# Main.net
KiCad netlist of a schematic drawn in Altium Designer
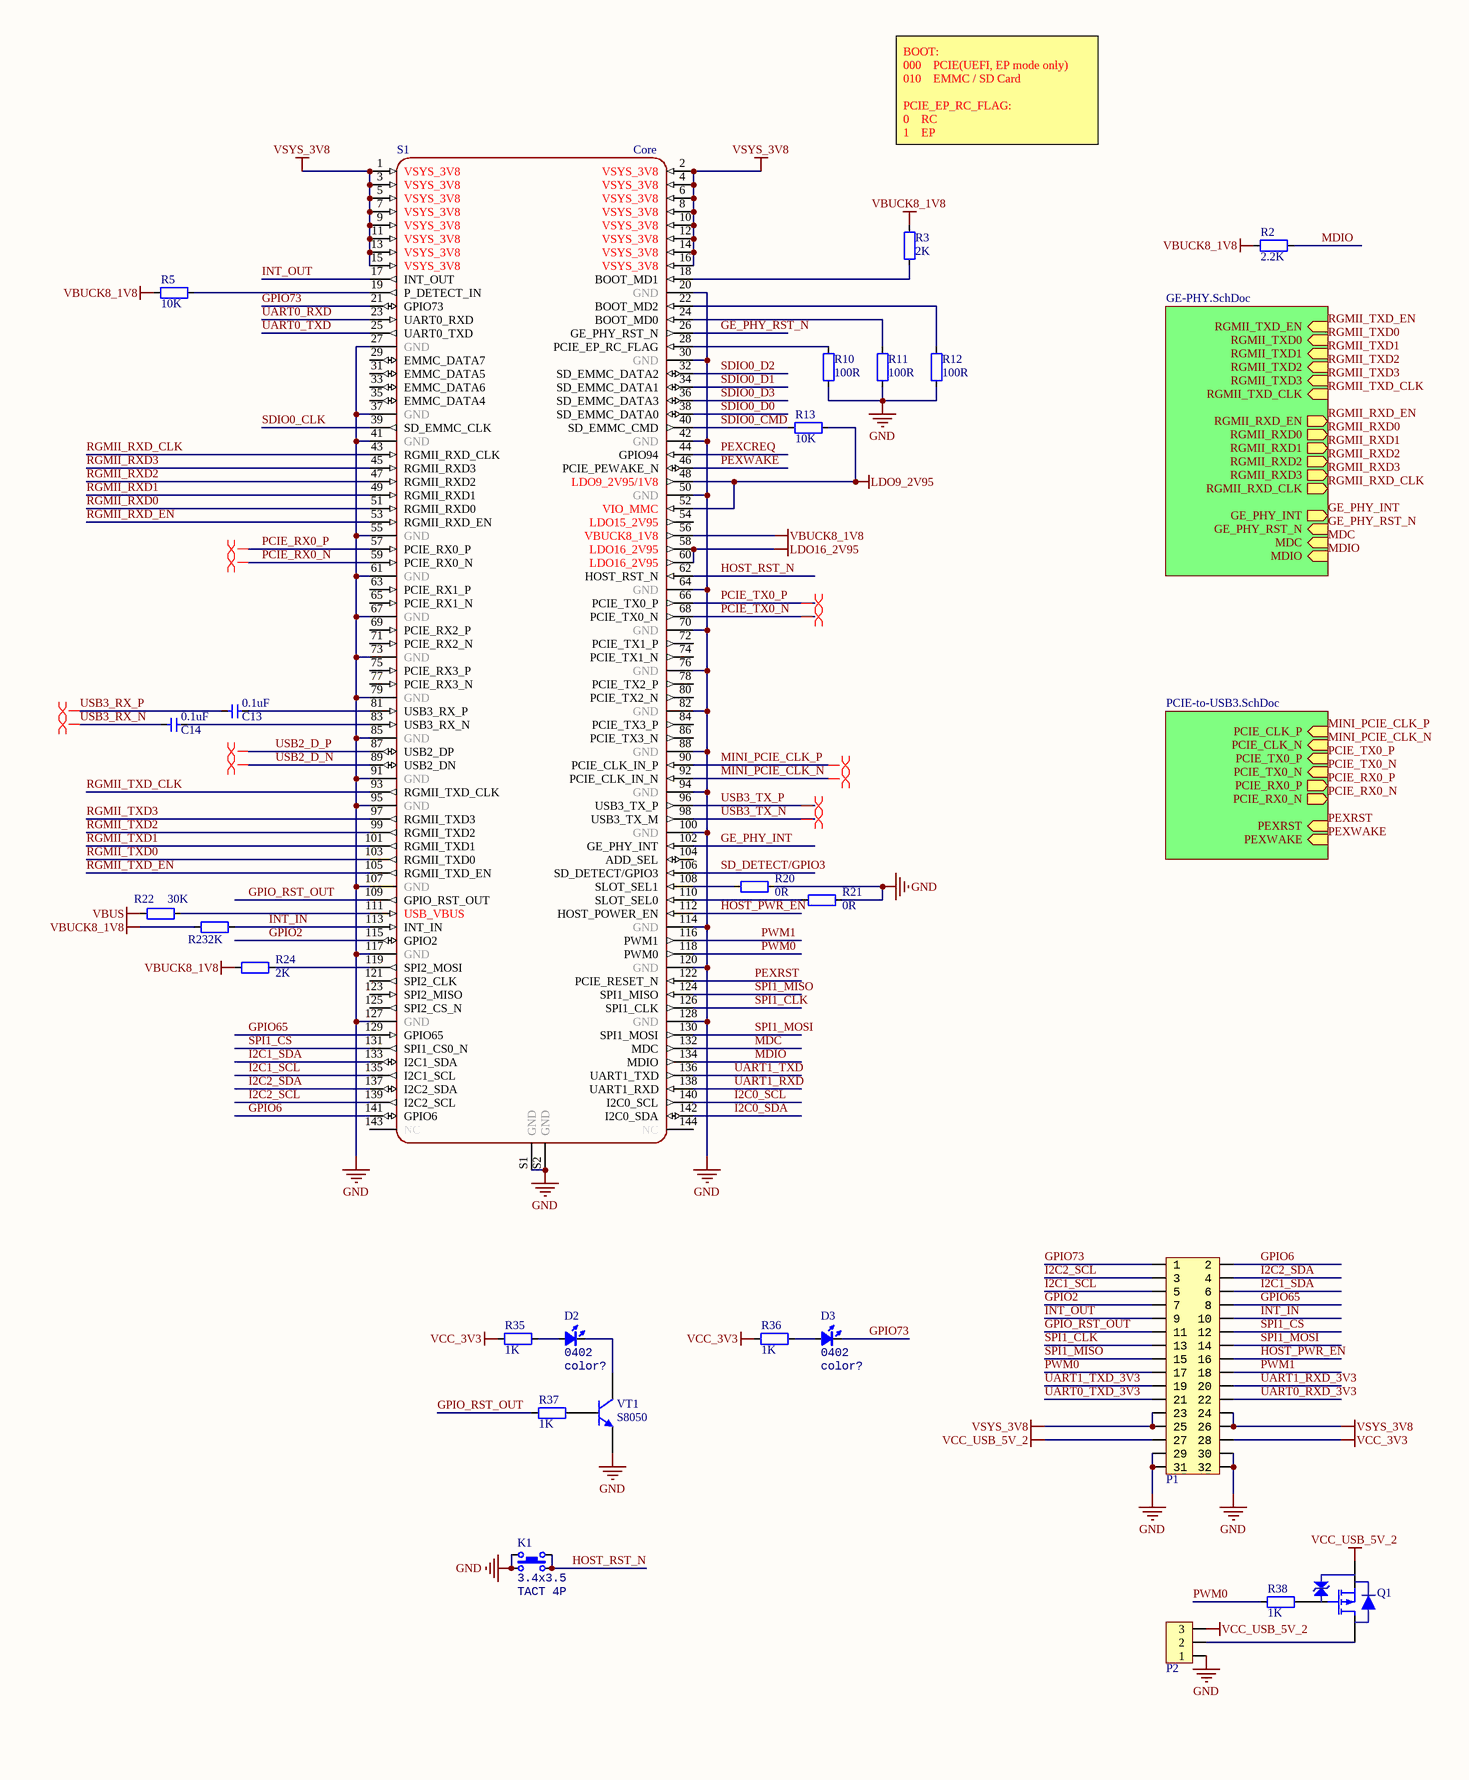
[diagram p0: Main.SchDoc, left]
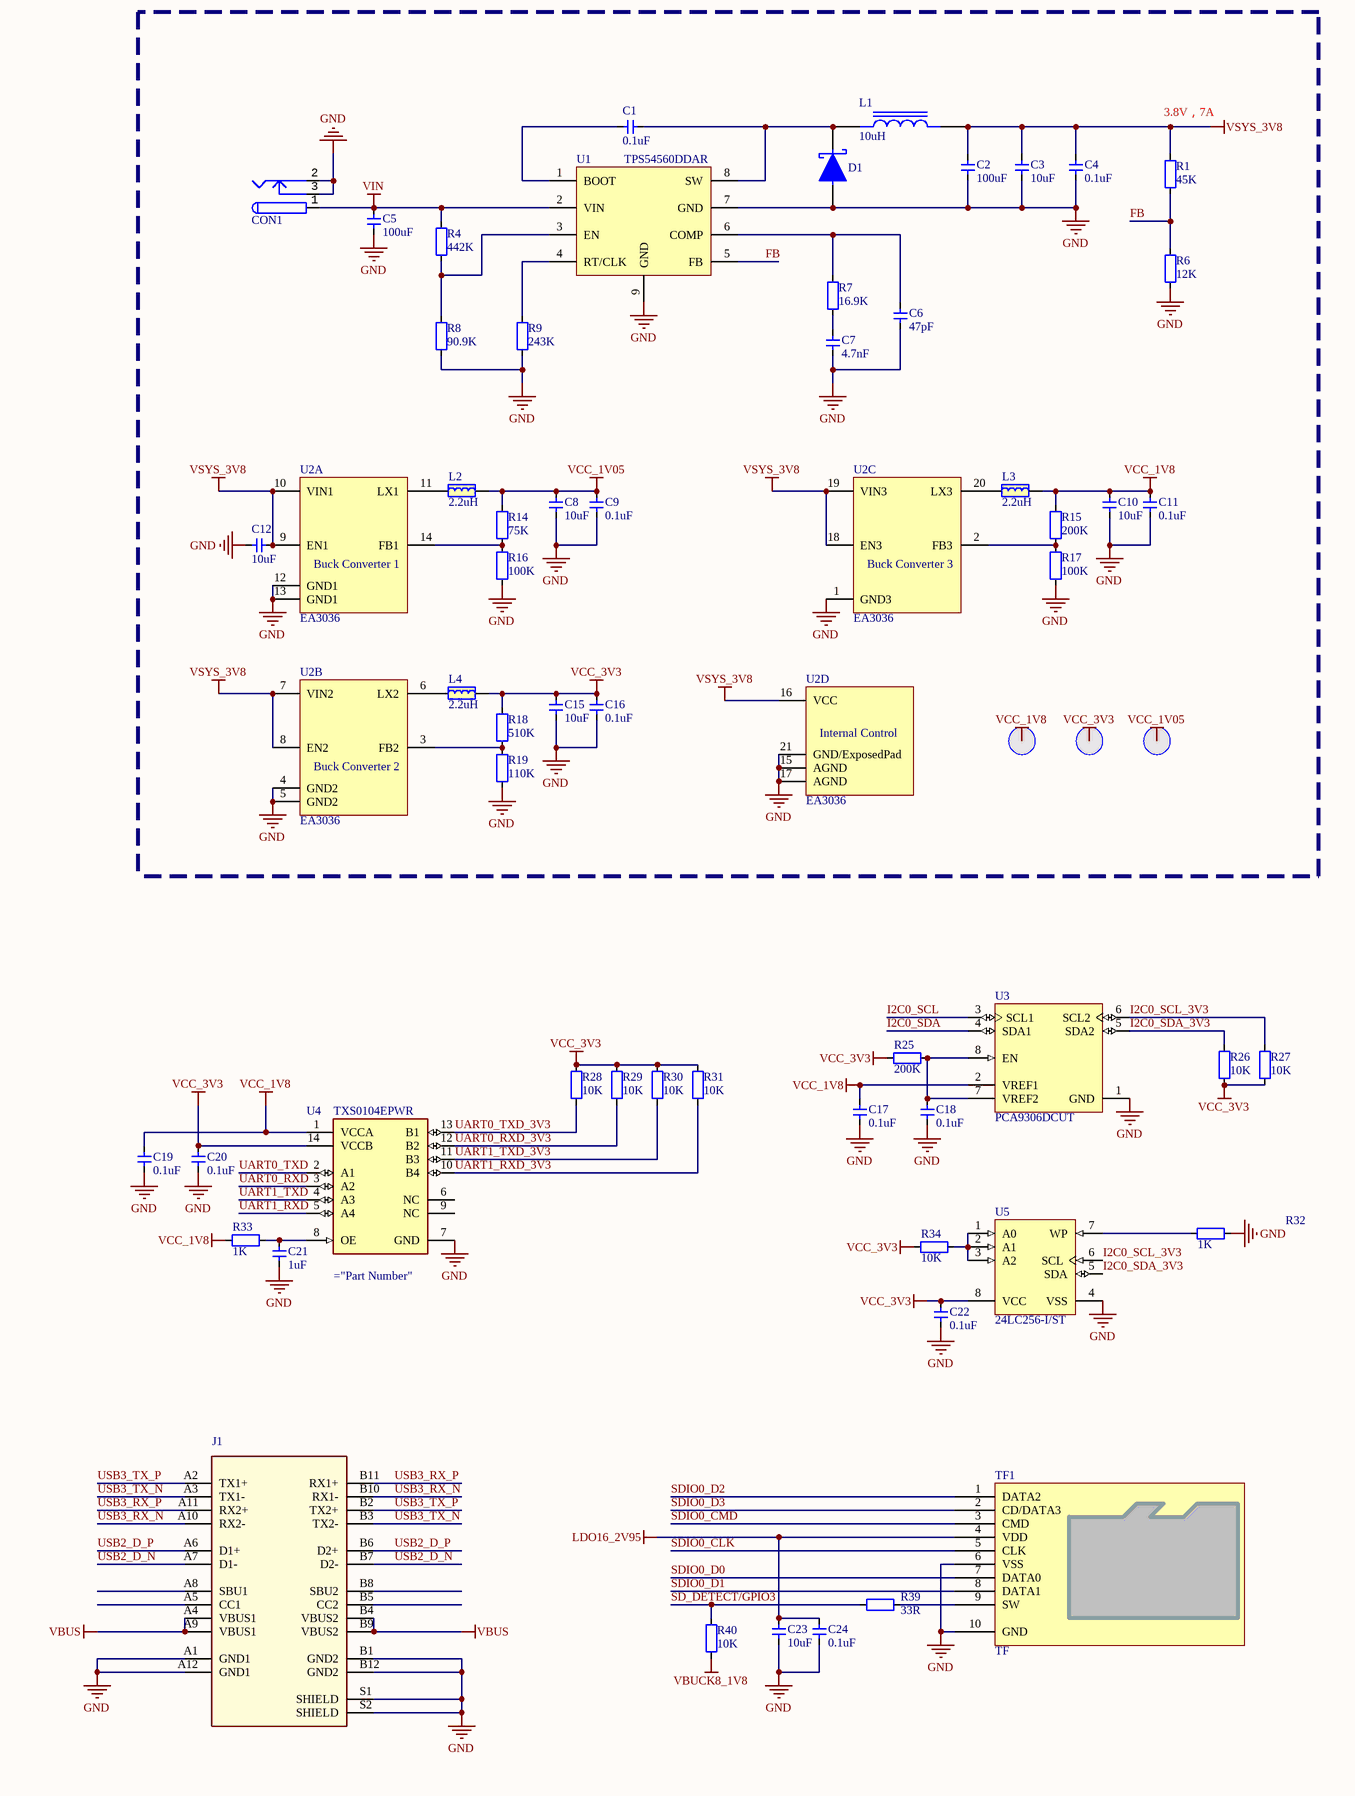
[diagram p1: Main.SchDoc, right]

(export (version "E")
  (design (tool "Eeschema 10.0.6"))
  (components
    (comp (ref "C1")
      (value "0.1uF")
      (footprint "CAP_0402")
      (description "Capacitor")
      (libsource (lib "MyPcbLib") (part "电容-0402"))
    )
    (comp (ref "C2")
      (value "100uF")
      (footprint "1206-CAP")
      (description "Capacitor")
      (libsource (lib "MyPcbLib") (part "电容-1206"))
    )
    (comp (ref "C3")
      (value "10uF")
      (footprint "CAP_0402")
      (description "Capacitor")
      (libsource (lib "MyPcbLib") (part "电容-0402"))
    )
    (comp (ref "C4")
      (value "0.1uF")
      (footprint "CAP_0402")
      (description "Capacitor")
      (libsource (lib "MyPcbLib") (part "电容-0402"))
    )
    (comp (ref "C5")
      (value "100uF")
      (footprint "1206-CAP")
      (description "Capacitor")
      (libsource (lib "MyPcbLib") (part "电容-1206"))
    )
    (comp (ref "C6")
      (value "47pF")
      (footprint "CAP_0402")
      (description "Capacitor")
      (libsource (lib "MyPcbLib") (part "电容-0402"))
    )
    (comp (ref "C7")
      (value "4.7nF")
      (footprint "CAP_0402")
      (description "Capacitor")
      (libsource (lib "MyPcbLib") (part "电容-0402"))
    )
    (comp (ref "C8")
      (value "10uF")
      (footprint "CAP_0402")
      (description "Capacitor")
      (libsource (lib "MyPcbLib") (part "电容-0402"))
    )
    (comp (ref "C9")
      (value "0.1uF")
      (footprint "CAP_0402")
      (description "Capacitor")
      (libsource (lib "MyPcbLib") (part "电容-0402"))
    )
    (comp (ref "C10")
      (value "10uF")
      (footprint "CAP_0402")
      (description "Capacitor")
      (libsource (lib "MyPcbLib") (part "电容-0402"))
    )
    (comp (ref "C11")
      (value "0.1uF")
      (footprint "CAP_0402")
      (description "Capacitor")
      (libsource (lib "MyPcbLib") (part "电容-0402"))
    )
    (comp (ref "C12")
      (value "10uF")
      (footprint "CAP_0402")
      (description "Capacitor")
      (libsource (lib "MyPcbLib") (part "电容-0402"))
    )
    (comp (ref "C13")
      (value "0.1uF")
      (footprint "CAP_0402")
      (description "Capacitor")
      (libsource (lib "MyPcbLib") (part "电容-0402"))
    )
    (comp (ref "C14")
      (value "0.1uF")
      (footprint "CAP_0402")
      (description "Capacitor")
      (libsource (lib "MyPcbLib") (part "电容-0402"))
    )
    (comp (ref "C15")
      (value "10uF")
      (footprint "CAP_0402")
      (description "Capacitor")
      (libsource (lib "MyPcbLib") (part "电容-0402"))
    )
    (comp (ref "C16")
      (value "0.1uF")
      (footprint "CAP_0402")
      (description "Capacitor")
      (libsource (lib "MyPcbLib") (part "电容-0402"))
    )
    (comp (ref "C17")
      (value "0.1uF")
      (footprint "CAP_0402")
      (description "Capacitor")
      (libsource (lib "MyPcbLib") (part "电容-0402"))
    )
    (comp (ref "C18")
      (value "0.1uF")
      (footprint "CAP_0402")
      (description "Capacitor")
      (libsource (lib "MyPcbLib") (part "电容-0402"))
    )
    (comp (ref "C19")
      (value "0.1uF")
      (footprint "CAP_0402")
      (description "Capacitor")
      (libsource (lib "MyPcbLib") (part "电容-0402"))
    )
    (comp (ref "C20")
      (value "0.1uF")
      (footprint "CAP_0402")
      (description "Capacitor")
      (libsource (lib "MyPcbLib") (part "电容-0402"))
    )
    (comp (ref "C21")
      (value "1uF")
      (footprint "CAP_0402")
      (description "Capacitor")
      (libsource (lib "MyPcbLib") (part "电容-0402"))
    )
    (comp (ref "C22")
      (value "0.1uF")
      (footprint "CAP_0402")
      (description "Capacitor")
      (libsource (lib "MyPcbLib") (part "电容-0402"))
    )
    (comp (ref "C23")
      (value "10uF")
      (footprint "CAP_0402")
      (description "Capacitor")
      (libsource (lib "MyPcbLib") (part "电容-0402"))
    )
    (comp (ref "C24")
      (value "0.1uF")
      (footprint "CAP_0402")
      (description "Capacitor")
      (libsource (lib "MyPcbLib") (part "电容-0402"))
    )
    (comp (ref "CON1")
      (value "PowerJack_2.5")
      (footprint "KLD_0202")
      (description "DC Power Jack")
      (libsource (lib "KitSprout") (part "PowerJack_2.5"))
    )
    (comp (ref "D1")
      (value "B560C-13-F")
      (footprint "DO-214AB-SMC")
      (libsource (lib "MyPcbLib") (part "B560C-13-F"))
    )
    (comp (ref "D2")
      (value "color?")
      (footprint "LED_0402_ORANGE")
      (description "LED")
      (fields (field (name "TYPE") "0402"))
      (libsource (lib "KitSprout") (part "LED_0402"))
    )
    (comp (ref "D3")
      (value "color?")
      (footprint "LED_0402_GREEN")
      (description "LED")
      (fields (field (name "TYPE") "0402"))
      (libsource (lib "KitSprout") (part "LED_0402"))
    )
    (comp (ref "J1")
      (value "USB-TYPE-C-TE")
      (footprint "USB TYPE C TE")
      (description "SPLASH PROOF USB TYPE C REC, DUAL SMT")
      (fields (field (name "MP") "2295018-2") (field (name "MF") "TE Connectivity"))
      (libsource (lib "MyPcbLib") (part "USB-TYPE-C-TE"))
    )
    (comp (ref "K1")
      (value "3.4x3.5")
      (footprint "ButtonTACT_3.5*3.55_90")
      (description "Button")
      (fields (field (name "TYPE") "TACT 4P") (field (name "Comment") "TACT 4P"))
      (libsource (lib "KitSprout") (part "ButtonTACT"))
    )
    (comp (ref "L1")
      (value "10uH")
      (footprint "IND_1040")
      (description "Fixed Inductors 4.7uH 30% SMD 1240")
      (fields (field (name "MF") "Bourns") (field (name "MP") "SRR1240-4R7Y"))
      (libsource (lib "MyPcbLib") (part "电感-1040"))
    )
    (comp (ref "L2")
      (value "2.2uH")
      (footprint "2520-L")
      (description "磁珠")
      (libsource (lib "MyPcbLib") (part "电感-2520"))
    )
    (comp (ref "L3")
      (value "2.2uH")
      (footprint "2520-L")
      (description "磁珠")
      (libsource (lib "MyPcbLib") (part "电感-2520"))
    )
    (comp (ref "L4")
      (value "2.2uH")
      (footprint "2520-L")
      (description "磁珠")
      (libsource (lib "MyPcbLib") (part "电感-2520"))
    )
    (comp (ref "P1")
      (value "HDR2x16_2.54")
      (footprint "HDR2X16_2.54_180")
      (description "Header")
      (libsource (lib "KitSprout") (part "HDR2x16_2.54"))
    )
    (comp (ref "P2")
      (value "HDR1x3_1.25")
      (footprint "接插件 3P")
      (description "Header")
      (libsource (lib "MyPcbLib") (part "HDR1x3_1.25"))
    )
    (comp (ref "Q1")
      (value "AO3415A")
      (footprint "SOT23-3")
      (description "MOSFET")
      (fields (field (name "PUBLISHER") "Altium Limited"))
      (libsource (lib "MyPcbLib") (part "AO3415A"))
    )
    (comp (ref "R1")
      (value "45K")
      (footprint "RES_0402")
      (description "Resistor")
      (libsource (lib "MyPcbLib") (part "电阻-0402"))
    )
    (comp (ref "R2")
      (value "2.2K")
      (footprint "RES_0402")
      (description "Resistor")
      (libsource (lib "") (part "电阻-0402_1"))
    )
    (comp (ref "R3")
      (value "2K")
      (footprint "RES_0402")
      (description "Resistor")
      (libsource (lib "") (part "电阻-0402_2"))
    )
    (comp (ref "R4")
      (value "442K")
      (footprint "RES_0402")
      (description "Resistor")
      (libsource (lib "MyPcbLib") (part "电阻-0402"))
    )
    (comp (ref "R5")
      (value "10K")
      (footprint "RES_0402")
      (description "Resistor")
      (libsource (lib "") (part "电阻-0402_1"))
    )
    (comp (ref "R6")
      (value "12K")
      (footprint "RES_0402")
      (description "Resistor")
      (libsource (lib "MyPcbLib") (part "电阻-0402"))
    )
    (comp (ref "R7")
      (value "16.9K")
      (footprint "RES_0402")
      (description "Resistor")
      (libsource (lib "MyPcbLib") (part "电阻-0402"))
    )
    (comp (ref "R8")
      (value "90.9K")
      (footprint "RES_0402")
      (description "Resistor")
      (libsource (lib "MyPcbLib") (part "电阻-0402"))
    )
    (comp (ref "R9")
      (value "243K")
      (footprint "RES_0402")
      (description "Resistor")
      (libsource (lib "MyPcbLib") (part "电阻-0402"))
    )
    (comp (ref "R10")
      (value "100R")
      (footprint "RES_0402")
      (description "Resistor")
      (libsource (lib "") (part "电阻-0402_2"))
    )
    (comp (ref "R11")
      (value "100R")
      (footprint "RES_0402")
      (description "Resistor")
      (libsource (lib "") (part "电阻-0402_2"))
    )
    (comp (ref "R12")
      (value "100R")
      (footprint "RES_0402")
      (description "Resistor")
      (libsource (lib "") (part "电阻-0402_2"))
    )
    (comp (ref "R13")
      (value "10K")
      (footprint "RES_0402")
      (description "Resistor")
      (libsource (lib "") (part "电阻-0402_1"))
    )
    (comp (ref "R14")
      (value "75K")
      (footprint "RES_0402")
      (description "Resistor")
      (libsource (lib "MyPcbLib") (part "电阻-0402"))
    )
    (comp (ref "R15")
      (value "200K")
      (footprint "RES_0402")
      (description "Resistor")
      (libsource (lib "MyPcbLib") (part "电阻-0402"))
    )
    (comp (ref "R16")
      (value "100K")
      (footprint "RES_0402")
      (description "Resistor")
      (libsource (lib "MyPcbLib") (part "电阻-0402"))
    )
    (comp (ref "R17")
      (value "100K")
      (footprint "RES_0402")
      (description "Resistor")
      (libsource (lib "MyPcbLib") (part "电阻-0402"))
    )
    (comp (ref "R18")
      (value "510K")
      (footprint "RES_0402")
      (description "Resistor")
      (libsource (lib "MyPcbLib") (part "电阻-0402"))
    )
    (comp (ref "R19")
      (value "110K")
      (footprint "RES_0402")
      (description "Resistor")
      (libsource (lib "MyPcbLib") (part "电阻-0402"))
    )
    (comp (ref "R20")
      (value "0R")
      (footprint "RES_0402")
      (description "Resistor")
      (libsource (lib "") (part "电阻-0402_3"))
    )
    (comp (ref "R21")
      (value "0R")
      (footprint "RES_0402")
      (description "Resistor")
      (libsource (lib "") (part "电阻-0402_3"))
    )
    (comp (ref "R22")
      (value "30K")
      (footprint "RES_0402")
      (description "Resistor")
      (libsource (lib "") (part "电阻-0402_3"))
    )
    (comp (ref "R23")
      (value "2K")
      (footprint "RES_0402")
      (description "Resistor")
      (libsource (lib "") (part "电阻-0402_3"))
    )
    (comp (ref "R24")
      (value "2K")
      (footprint "RES_0402")
      (description "Resistor")
      (libsource (lib "") (part "电阻-0402_3"))
    )
    (comp (ref "R25")
      (value "200K")
      (footprint "RES_0402")
      (description "Resistor")
      (libsource (lib "") (part "电阻-0402_1"))
    )
    (comp (ref "R26")
      (value "10K")
      (footprint "RES_0402")
      (description "Resistor")
      (libsource (lib "MyPcbLib") (part "电阻-0402"))
    )
    (comp (ref "R27")
      (value "10K")
      (footprint "RES_0402")
      (description "Resistor")
      (libsource (lib "MyPcbLib") (part "电阻-0402"))
    )
    (comp (ref "R28")
      (value "10K")
      (footprint "RES_0402")
      (description "Resistor")
      (libsource (lib "") (part "电阻-0402_2"))
    )
    (comp (ref "R29")
      (value "10K")
      (footprint "RES_0402")
      (description "Resistor")
      (libsource (lib "") (part "电阻-0402_2"))
    )
    (comp (ref "R30")
      (value "10K")
      (footprint "RES_0402")
      (description "Resistor")
      (libsource (lib "") (part "电阻-0402_2"))
    )
    (comp (ref "R31")
      (value "10K")
      (footprint "RES_0402")
      (description "Resistor")
      (libsource (lib "") (part "电阻-0402_2"))
    )
    (comp (ref "R32")
      (value "1K")
      (footprint "RES_0402")
      (description "Resistor")
      (libsource (lib "") (part "电阻-0402_3"))
    )
    (comp (ref "R33")
      (value "1K")
      (footprint "RES_0402")
      (description "Resistor")
      (libsource (lib "") (part "电阻-0402_3"))
    )
    (comp (ref "R34")
      (value "10K")
      (footprint "RES_0402")
      (description "Resistor")
      (libsource (lib "") (part "电阻-0402_3"))
    )
    (comp (ref "R35")
      (value "1K")
      (footprint "RES_0402")
      (description "Resistor")
      (libsource (lib "") (part "电阻-0402_1"))
    )
    (comp (ref "R36")
      (value "1K")
      (footprint "RES_0402")
      (description "Resistor")
      (libsource (lib "") (part "电阻-0402_1"))
    )
    (comp (ref "R37")
      (value "1K")
      (footprint "RES_0402")
      (description "Resistor")
      (libsource (lib "") (part "电阻-0402_1"))
    )
    (comp (ref "R38")
      (value "1K")
      (footprint "RES_0402")
      (description "Resistor")
      (libsource (lib "") (part "电阻-0402_1"))
    )
    (comp (ref "R39")
      (value "33R")
      (footprint "RES_0402")
      (description "Resistor")
      (libsource (lib "") (part "电阻-0402_3"))
    )
    (comp (ref "R40")
      (value "10K")
      (footprint "RES_0402")
      (description "Resistor")
      (libsource (lib "MyPcbLib") (part "电阻-0402"))
    )
    (comp (ref "S1")
      (value "Core")
      (footprint "ATLAS-200")
      (description "Atlas-A200 AI-SOM")
      (libsource (lib "SOM") (part "Atlas-200"))
    )
    (comp (ref "T1") (value "测试点") (footprint "TEST_PT") (libsource (lib "MyPcbLib") (part "测试点")))
    (comp (ref "T2") (value "测试点") (footprint "TEST_PT") (libsource (lib "MyPcbLib") (part "测试点")))
    (comp (ref "T3") (value "测试点") (footprint "TEST_PT") (libsource (lib "MyPcbLib") (part "测试点")))
    (comp (ref "TF1")
      (value "TF")
      (footprint "TF-SOCKET")
      (description "8脚自弹")
      (libsource (lib "MyPcbLib") (part "TF卡座"))
    )
    (comp (ref "U1")
      (value "TPS54560DDAR")
      (footprint "SO-8-PAD")
      (description "DC-DC Convter")
      (libsource (lib "MyPcbLib") (part "TPS54560DDAR"))
    )
    (comp (ref "U2") (value "EA3036") (footprint "QFN-20") (libsource (lib "MyPcbLib") (part "EA3036")))
    (comp (ref "U3")
      (value "PCA9306DCUT")
      (footprint "VSSOP-8")
      (fields (field (name "MANUFACTURER") "Texas Instruments"))
      (libsource (lib "MyPcbLib") (part "PCA9306DCUT"))
    )
    (comp (ref "U4")
      (value "TXS0104EPWR")
      (footprint "R-PDSO-G14")
      (libsource (lib "MyPcbLib") (part "TXS0104EPWR"))
    )
    (comp (ref "U5")
      (value "24LC256-I/ST")
      (footprint "TSSOP-8")
      (description "256Kbit, 400kHz, 2.5V, I2C Serial EEPROM, 8-Pin TSSOP, Industrial Temperature")
      (libsource (lib "MyPcbLib") (part "24LC256-I/ST"))
    )
    (comp (ref "VT1")
      (value "S8050")
      (footprint "SMT_TRIODE_NPN")
      (description "Surface mount NPN transistor, package SOT-23")
      (libsource (lib "MyPcbLib") (part "SMT_TRIODE_NPN"))
    )
  )
  (nets
    (net (code "1") (name "/FB") (class "Default")
      (node (ref "R1") (pin "1") (pinfunction "1_1") (pintype "passive"))
      (node (ref "R6") (pin "2") (pinfunction "2_2") (pintype "passive"))
      (node (ref "U1") (pin "5") (pinfunction "FB_5") (pintype "passive"))
    )
    (net (code "2") (name "/GE_PHY_INT") (class "Default")
      (node (ref "S1") (pin "102") (pinfunction "GE_PHY_INT_102") (pintype "input"))
    )
    (net (code "3") (name "/GE_PHY_RST_N") (class "Default")
      (node (ref "S1") (pin "26") (pinfunction "GE_PHY_RST_N_26") (pintype "output"))
    )
    (net (code "4") (name "/GPIO2") (class "Default")
      (node (ref "P1") (pin "7") (pinfunction "7_7") (pintype "passive"))
      (node (ref "S1") (pin "115") (pinfunction "GPIO2_115") (pintype "bidirectional"))
    )
    (net (code "5") (name "/GPIO6") (class "Default")
      (node (ref "P1") (pin "2") (pinfunction "2_2") (pintype "passive"))
      (node (ref "S1") (pin "141") (pinfunction "GPIO6_141") (pintype "bidirectional"))
    )
    (net (code "6") (name "/GPIO65") (class "Default")
      (node (ref "P1") (pin "8") (pinfunction "8_8") (pintype "passive"))
      (node (ref "S1") (pin "129") (pinfunction "GPIO65_129") (pintype "input"))
    )
    (net (code "7") (name "/GPIO73") (class "Default")
      (node (ref "D3") (pin "2") (pinfunction "K_2") (pintype "passive"))
      (node (ref "P1") (pin "1") (pinfunction "1_1") (pintype "passive"))
      (node (ref "S1") (pin "21") (pinfunction "GPIO73_21") (pintype "bidirectional"))
    )
    (net (code "8") (name "/GPIO_RST_OUT") (class "Default")
      (node (ref "P1") (pin "11") (pinfunction "11_11") (pintype "passive"))
      (node (ref "R37") (pin "1") (pinfunction "1_1") (pintype "passive"))
      (node (ref "S1") (pin "109") (pinfunction "GPIO_RST_OUT_109") (pintype "output"))
    )
    (net (code "9") (name "/HOST_PWR_EN") (class "Default")
      (node (ref "P1") (pin "16") (pinfunction "16_16") (pintype "passive"))
      (node (ref "S1") (pin "112") (pinfunction "HOST_POWER_EN_112") (pintype "input"))
    )
    (net (code "10") (name "/HOST_RST_N") (class "Default")
      (node (ref "K1") (pin "2") (pinfunction "2_2") (pintype "passive"))
      (node (ref "K1") (pin "4") (pinfunction "4_4") (pintype "passive"))
      (node (ref "S1") (pin "62") (pinfunction "HOST_RST_N_62") (pintype "input"))
    )
    (net (code "11") (name "/I2C0_SCL") (class "Default")
      (node (ref "S1") (pin "140") (pinfunction "I2C0_SCL_140") (pintype "output"))
      (node (ref "U3") (pin "3") (pinfunction "SCL1_3") (pintype "bidirectional"))
    )
    (net (code "12") (name "/I2C0_SCL_3V3") (class "Default")
      (node (ref "R27") (pin "2") (pinfunction "2_2") (pintype "passive"))
      (node (ref "U3") (pin "6") (pinfunction "SCL2_6") (pintype "bidirectional"))
      (node (ref "U5") (pin "6") (pinfunction "SCL_6") (pintype "input"))
    )
    (net (code "13") (name "/I2C0_SDA") (class "Default")
      (node (ref "S1") (pin "142") (pinfunction "I2C0_SDA_142") (pintype "bidirectional"))
      (node (ref "U3") (pin "4") (pinfunction "SDA1_4") (pintype "bidirectional"))
    )
    (net (code "14") (name "/I2C0_SDA_3V3") (class "Default")
      (node (ref "R26") (pin "2") (pinfunction "2_2") (pintype "passive"))
      (node (ref "U3") (pin "5") (pinfunction "SDA2_5") (pintype "bidirectional"))
      (node (ref "U5") (pin "5") (pinfunction "SDA_5") (pintype "bidirectional"))
    )
    (net (code "15") (name "/I2C1_SCL") (class "Default")
      (node (ref "P1") (pin "5") (pinfunction "5_5") (pintype "passive"))
      (node (ref "S1") (pin "135") (pinfunction "I2C1_SCL_135") (pintype "output"))
    )
    (net (code "16") (name "/I2C1_SDA") (class "Default")
      (node (ref "P1") (pin "6") (pinfunction "6_6") (pintype "passive"))
      (node (ref "S1") (pin "133") (pinfunction "I2C1_SDA_133") (pintype "bidirectional"))
    )
    (net (code "17") (name "/I2C2_SCL") (class "Default")
      (node (ref "P1") (pin "3") (pinfunction "3_3") (pintype "passive"))
      (node (ref "S1") (pin "139") (pinfunction "I2C2_SCL_139") (pintype "output"))
    )
    (net (code "18") (name "/I2C2_SDA") (class "Default")
      (node (ref "P1") (pin "4") (pinfunction "4_4") (pintype "passive"))
      (node (ref "S1") (pin "137") (pinfunction "I2C2_SDA_137") (pintype "bidirectional"))
    )
    (net (code "19") (name "/INT_IN") (class "Default")
      (node (ref "P1") (pin "10") (pinfunction "10_10") (pintype "passive"))
      (node (ref "R23") (pin "1") (pinfunction "1_1") (pintype "passive"))
      (node (ref "S1") (pin "113") (pinfunction "INT_IN_113") (pintype "input"))
    )
    (net (code "20") (name "/INT_OUT") (class "Default")
      (node (ref "P1") (pin "9") (pinfunction "9_9") (pintype "passive"))
      (node (ref "S1") (pin "17") (pinfunction "INT_OUT_17") (pintype "output"))
    )
    (net (code "21") (name "/MDC") (class "Default")
      (node (ref "S1") (pin "132") (pinfunction "MDC_132") (pintype "output"))
    )
    (net (code "22") (name "/MDIO") (class "Default")
      (node (ref "R2") (pin "2") (pinfunction "2_2") (pintype "passive"))
      (node (ref "S1") (pin "134") (pinfunction "MDIO_134") (pintype "output"))
    )
    (net (code "23") (name "/MINI_PCIE_CLK_N") (class "Default")
      (node (ref "S1") (pin "92") (pinfunction "PCIE_CLK_IN_N_92") (pintype "input"))
    )
    (net (code "24") (name "/MINI_PCIE_CLK_P") (class "Default")
      (node (ref "S1") (pin "90") (pinfunction "PCIE_CLK_IN_P_90") (pintype "input"))
    )
    (net (code "25") (name "/PCIE_RX0_N") (class "Default")
      (node (ref "S1") (pin "59") (pinfunction "PCIE_RX0_N_59") (pintype "input"))
    )
    (net (code "26") (name "/PCIE_RX0_P") (class "Default")
      (node (ref "S1") (pin "57") (pinfunction "PCIE_RX0_P_57") (pintype "input"))
    )
    (net (code "27") (name "/PCIE_TX0_N") (class "Default")
      (node (ref "S1") (pin "68") (pinfunction "PCIE_TX0_N_68") (pintype "output"))
    )
    (net (code "28") (name "/PCIE_TX0_P") (class "Default")
      (node (ref "S1") (pin "66") (pinfunction "PCIE_TX0_P_66") (pintype "output"))
    )
    (net (code "29") (name "/PEXCREQ") (class "Default")
      (node (ref "S1") (pin "44") (pinfunction "GPIO94_44") (pintype "input"))
    )
    (net (code "30") (name "/PEXRST") (class "Default")
      (node (ref "S1") (pin "122") (pinfunction "PCIE_RESET_N_122") (pintype "input"))
    )
    (net (code "31") (name "/PEXWAKE") (class "Default")
      (node (ref "S1") (pin "46") (pinfunction "PCIE_PEWAKE_N_46") (pintype "bidirectional"))
    )
    (net (code "32") (name "/PWM0") (class "Default")
      (node (ref "P1") (pin "17") (pinfunction "17_17") (pintype "passive"))
      (node (ref "R38") (pin "1") (pinfunction "1_1") (pintype "passive"))
      (node (ref "S1") (pin "118") (pinfunction "PWM0_118") (pintype "output"))
    )
    (net (code "33") (name "/PWM1") (class "Default")
      (node (ref "P1") (pin "18") (pinfunction "18_18") (pintype "passive"))
      (node (ref "S1") (pin "116") (pinfunction "PWM1_116") (pintype "output"))
    )
    (net (code "34") (name "/RGMII_RXD0") (class "Default")
      (node (ref "S1") (pin "51") (pinfunction "RGMII_RXD0_51") (pintype "input"))
    )
    (net (code "35") (name "/RGMII_RXD1") (class "Default")
      (node (ref "S1") (pin "49") (pinfunction "RGMII_RXD1_49") (pintype "input"))
    )
    (net (code "36") (name "/RGMII_RXD2") (class "Default")
      (node (ref "S1") (pin "47") (pinfunction "RGMII_RXD2_47") (pintype "input"))
    )
    (net (code "37") (name "/RGMII_RXD3") (class "Default")
      (node (ref "S1") (pin "45") (pinfunction "RGMII_RXD3_45") (pintype "input"))
    )
    (net (code "38") (name "/RGMII_RXD_CLK") (class "Default")
      (node (ref "S1") (pin "43") (pinfunction "RGMII_RXD_CLK_43") (pintype "input"))
    )
    (net (code "39") (name "/RGMII_RXD_EN") (class "Default")
      (node (ref "S1") (pin "53") (pinfunction "RGMII_RXD_EN_53") (pintype "input"))
    )
    (net (code "40") (name "/RGMII_TXD0") (class "Default")
      (node (ref "S1") (pin "103") (pinfunction "RGMII_TXD0_103") (pintype "output"))
    )
    (net (code "41") (name "/RGMII_TXD1") (class "Default")
      (node (ref "S1") (pin "101") (pinfunction "RGMII_TXD1_101") (pintype "output"))
    )
    (net (code "42") (name "/RGMII_TXD2") (class "Default")
      (node (ref "S1") (pin "99") (pinfunction "RGMII_TXD2_99") (pintype "output"))
    )
    (net (code "43") (name "/RGMII_TXD3") (class "Default")
      (node (ref "S1") (pin "97") (pinfunction "RGMII_TXD3_97") (pintype "output"))
    )
    (net (code "44") (name "/RGMII_TXD_CLK") (class "Default")
      (node (ref "S1") (pin "93") (pinfunction "RGMII_TXD_CLK_93") (pintype "output"))
    )
    (net (code "45") (name "/RGMII_TXD_EN") (class "Default")
      (node (ref "S1") (pin "105") (pinfunction "RGMII_TXD_EN_105") (pintype "output"))
    )
    (net (code "46") (name "/SDIO0_CLK") (class "Default")
      (node (ref "S1") (pin "39") (pinfunction "SD_EMMC_CLK_39") (pintype "output"))
      (node (ref "TF1") (pin "5") (pinfunction "CLK_5") (pintype "passive"))
    )
    (net (code "47") (name "/SDIO0_CMD") (class "Default")
      (node (ref "R13") (pin "1") (pinfunction "1_1") (pintype "passive"))
      (node (ref "S1") (pin "40") (pinfunction "SD_EMMC_CMD_40") (pintype "output"))
      (node (ref "TF1") (pin "3") (pinfunction "CMD_3") (pintype "passive"))
    )
    (net (code "48") (name "/SDIO0_D0") (class "Default")
      (node (ref "S1") (pin "38") (pinfunction "SD_EMMC_DATA0_38") (pintype "bidirectional"))
      (node (ref "TF1") (pin "7") (pinfunction "DATA0_7") (pintype "passive"))
    )
    (net (code "49") (name "/SDIO0_D1") (class "Default")
      (node (ref "S1") (pin "34") (pinfunction "SD_EMMC_DATA1_34") (pintype "bidirectional"))
      (node (ref "TF1") (pin "8") (pinfunction "DATA1_8") (pintype "passive"))
    )
    (net (code "50") (name "/SDIO0_D2") (class "Default")
      (node (ref "S1") (pin "32") (pinfunction "SD_EMMC_DATA2_32") (pintype "bidirectional"))
      (node (ref "TF1") (pin "1") (pinfunction "DATA2_1") (pintype "passive"))
    )
    (net (code "51") (name "/SDIO0_D3") (class "Default")
      (node (ref "S1") (pin "36") (pinfunction "SD_EMMC_DATA3_36") (pintype "bidirectional"))
      (node (ref "TF1") (pin "2") (pinfunction "CD/DATA3_2") (pintype "passive"))
    )
    (net (code "52") (name "/SD_DETECT{slash}GPIO3") (class "Default")
      (node (ref "R39") (pin "2") (pinfunction "2_2") (pintype "passive"))
      (node (ref "R40") (pin "2") (pinfunction "2_2") (pintype "passive"))
      (node (ref "S1") (pin "106") (pinfunction "SD_DETECT/GPIO3_106") (pintype "input"))
    )
    (net (code "53") (name "/SPI1_CLK") (class "Default")
      (node (ref "P1") (pin "13") (pinfunction "13_13") (pintype "passive"))
      (node (ref "S1") (pin "126") (pinfunction "SPI1_CLK_126") (pintype "output"))
    )
    (net (code "54") (name "/SPI1_CS") (class "Default")
      (node (ref "P1") (pin "12") (pinfunction "12_12") (pintype "passive"))
      (node (ref "S1") (pin "131") (pinfunction "SPI1_CS0_N_131") (pintype "output"))
    )
    (net (code "55") (name "/SPI1_MISO") (class "Default")
      (node (ref "P1") (pin "15") (pinfunction "15_15") (pintype "passive"))
      (node (ref "S1") (pin "124") (pinfunction "SPI1_MISO_124") (pintype "input"))
    )
    (net (code "56") (name "/SPI1_MOSI") (class "Default")
      (node (ref "P1") (pin "14") (pinfunction "14_14") (pintype "passive"))
      (node (ref "S1") (pin "130") (pinfunction "SPI1_MOSI_130") (pintype "output"))
    )
    (net (code "57") (name "/UART0_RXD") (class "Default")
      (node (ref "S1") (pin "23") (pinfunction "UART0_RXD_23") (pintype "input"))
      (node (ref "U4") (pin "3") (pinfunction "A2_3") (pintype "bidirectional"))
    )
    (net (code "58") (name "/UART0_RXD_3V3") (class "Default")
      (node (ref "P1") (pin "22") (pinfunction "22_22") (pintype "passive"))
      (node (ref "R29") (pin "2") (pinfunction "2_2") (pintype "passive"))
      (node (ref "U4") (pin "12") (pinfunction "B2_12") (pintype "bidirectional"))
    )
    (net (code "59") (name "/UART0_TXD") (class "Default")
      (node (ref "S1") (pin "25") (pinfunction "UART0_TXD_25") (pintype "output"))
      (node (ref "U4") (pin "2") (pinfunction "A1_2") (pintype "bidirectional"))
    )
    (net (code "60") (name "/UART0_TXD_3V3") (class "Default")
      (node (ref "P1") (pin "21") (pinfunction "21_21") (pintype "passive"))
      (node (ref "R28") (pin "2") (pinfunction "2_2") (pintype "passive"))
      (node (ref "U4") (pin "13") (pinfunction "B1_13") (pintype "bidirectional"))
    )
    (net (code "61") (name "/UART1_RXD") (class "Default")
      (node (ref "S1") (pin "138") (pinfunction "UART1_RXD_138") (pintype "input"))
      (node (ref "U4") (pin "5") (pinfunction "A4_5") (pintype "bidirectional"))
    )
    (net (code "62") (name "/UART1_RXD_3V3") (class "Default")
      (node (ref "P1") (pin "20") (pinfunction "20_20") (pintype "passive"))
      (node (ref "R31") (pin "2") (pinfunction "2_2") (pintype "passive"))
      (node (ref "U4") (pin "10") (pinfunction "B4_10") (pintype "bidirectional"))
    )
    (net (code "63") (name "/UART1_TXD") (class "Default")
      (node (ref "S1") (pin "136") (pinfunction "UART1_TXD_136") (pintype "output"))
      (node (ref "U4") (pin "4") (pinfunction "A3_4") (pintype "bidirectional"))
    )
    (net (code "64") (name "/UART1_TXD_3V3") (class "Default")
      (node (ref "P1") (pin "19") (pinfunction "19_19") (pintype "passive"))
      (node (ref "R30") (pin "2") (pinfunction "2_2") (pintype "passive"))
      (node (ref "U4") (pin "11") (pinfunction "B3_11") (pintype "bidirectional"))
    )
    (net (code "65") (name "/USB2_D_N") (class "Default")
      (node (ref "J1") (pin "A7") (pinfunction "D1-_A7") (pintype "passive"))
      (node (ref "J1") (pin "B7") (pinfunction "D2-_B7") (pintype "passive"))
      (node (ref "S1") (pin "89") (pinfunction "USB2_DN_89") (pintype "bidirectional"))
    )
    (net (code "66") (name "/USB2_D_P") (class "Default")
      (node (ref "J1") (pin "A6") (pinfunction "D1+_A6") (pintype "passive"))
      (node (ref "J1") (pin "B6") (pinfunction "D2+_B6") (pintype "passive"))
      (node (ref "S1") (pin "87") (pinfunction "USB2_DP_87") (pintype "bidirectional"))
    )
    (net (code "67") (name "/USB3_RX_N") (class "Default")
      (node (ref "C14") (pin "2") (pinfunction "2_2") (pintype "passive"))
      (node (ref "J1") (pin "A10") (pinfunction "RX2-_A10") (pintype "passive"))
      (node (ref "J1") (pin "B10") (pinfunction "RX1-_B10") (pintype "passive"))
    )
    (net (code "68") (name "/USB3_RX_P") (class "Default")
      (node (ref "C13") (pin "2") (pinfunction "2_2") (pintype "passive"))
      (node (ref "J1") (pin "A11") (pinfunction "RX2+_A11") (pintype "passive"))
      (node (ref "J1") (pin "B11") (pinfunction "RX1+_B11") (pintype "passive"))
    )
    (net (code "69") (name "/USB3_TX_N") (class "Default")
      (node (ref "J1") (pin "A3") (pinfunction "TX1-_A3") (pintype "passive"))
      (node (ref "J1") (pin "B3") (pinfunction "TX2-_B3") (pintype "passive"))
      (node (ref "S1") (pin "98") (pinfunction "USB3_TX_M_98") (pintype "output"))
    )
    (net (code "70") (name "/USB3_TX_P") (class "Default")
      (node (ref "J1") (pin "A2") (pinfunction "TX1+_A2") (pintype "passive"))
      (node (ref "J1") (pin "B2") (pinfunction "TX2+_B2") (pintype "passive"))
      (node (ref "S1") (pin "96") (pinfunction "USB3_TX_P_96") (pintype "output"))
    )
    (net (code "71") (name "GND") (class "Default")
      (node (ref "C10") (pin "2") (pinfunction "2_2") (pintype "passive"))
      (node (ref "C11") (pin "2") (pinfunction "2_2") (pintype "passive"))
      (node (ref "C12") (pin "1") (pinfunction "1_1") (pintype "passive"))
      (node (ref "C15") (pin "2") (pinfunction "2_2") (pintype "passive"))
      (node (ref "C16") (pin "2") (pinfunction "2_2") (pintype "passive"))
      (node (ref "C17") (pin "1") (pinfunction "1_1") (pintype "passive"))
      (node (ref "C18") (pin "1") (pinfunction "1_1") (pintype "passive"))
      (node (ref "C19") (pin "1") (pinfunction "1_1") (pintype "passive"))
      (node (ref "C2") (pin "1") (pinfunction "1_1") (pintype "passive"))
      (node (ref "C20") (pin "1") (pinfunction "1_1") (pintype "passive"))
      (node (ref "C21") (pin "1") (pinfunction "1_1") (pintype "passive"))
      (node (ref "C22") (pin "1") (pinfunction "1_1") (pintype "passive"))
      (node (ref "C23") (pin "2") (pinfunction "2_2") (pintype "passive"))
      (node (ref "C24") (pin "2") (pinfunction "2_2") (pintype "passive"))
      (node (ref "C3") (pin "2") (pinfunction "2_2") (pintype "passive"))
      (node (ref "C4") (pin "2") (pinfunction "2_2") (pintype "passive"))
      (node (ref "C5") (pin "1") (pinfunction "1_1") (pintype "passive"))
      (node (ref "C6") (pin "1") (pinfunction "1_1") (pintype "passive"))
      (node (ref "C7") (pin "1") (pinfunction "1_1") (pintype "passive"))
      (node (ref "C8") (pin "2") (pinfunction "2_2") (pintype "passive"))
      (node (ref "C9") (pin "2") (pinfunction "2_2") (pintype "passive"))
      (node (ref "CON1") (pin "2") (pinfunction "2_2") (pintype "power_in"))
      (node (ref "CON1") (pin "3") (pinfunction "3_3") (pintype "power_in"))
      (node (ref "D1") (pin "2") (pinfunction "A_2") (pintype "passive"))
      (node (ref "J1") (pin "A1") (pinfunction "GND1_A1") (pintype "passive"))
      (node (ref "J1") (pin "A12") (pinfunction "GND1_A12") (pintype "passive"))
      (node (ref "J1") (pin "B1") (pinfunction "GND2_B1") (pintype "passive"))
      (node (ref "J1") (pin "B12") (pinfunction "GND2_B12") (pintype "passive"))
      (node (ref "J1") (pin "S1") (pinfunction "SHIELD_S1") (pintype "passive"))
      (node (ref "J1") (pin "S2") (pinfunction "SHIELD_S2") (pintype "passive"))
      (node (ref "K1") (pin "1") (pinfunction "1_1") (pintype "passive"))
      (node (ref "K1") (pin "3") (pinfunction "3_3") (pintype "passive"))
      (node (ref "P1") (pin "29") (pinfunction "29_29") (pintype "passive"))
      (node (ref "P1") (pin "30") (pinfunction "30_30") (pintype "passive"))
      (node (ref "P1") (pin "31") (pinfunction "31_31") (pintype "passive"))
      (node (ref "P1") (pin "32") (pinfunction "32_32") (pintype "passive"))
      (node (ref "P2") (pin "1") (pinfunction "1_1") (pintype "passive"))
      (node (ref "R10") (pin "2") (pinfunction "2_2") (pintype "passive"))
      (node (ref "R11") (pin "2") (pinfunction "2_2") (pintype "passive"))
      (node (ref "R12") (pin "2") (pinfunction "2_2") (pintype "passive"))
      (node (ref "R16") (pin "1") (pinfunction "1_1") (pintype "passive"))
      (node (ref "R17") (pin "1") (pinfunction "1_1") (pintype "passive"))
      (node (ref "R19") (pin "1") (pinfunction "1_1") (pintype "passive"))
      (node (ref "R20") (pin "1") (pinfunction "1_1") (pintype "passive"))
      (node (ref "R21") (pin "1") (pinfunction "1_1") (pintype "passive"))
      (node (ref "R32") (pin "1") (pinfunction "1_1") (pintype "passive"))
      (node (ref "R6") (pin "1") (pinfunction "1_1") (pintype "passive"))
      (node (ref "R8") (pin "1") (pinfunction "1_1") (pintype "passive"))
      (node (ref "R9") (pin "1") (pinfunction "1_1") (pintype "passive"))
      (node (ref "S1") (pin "100") (pinfunction "GND_100") (pintype "power_in"))
      (node (ref "S1") (pin "107") (pinfunction "GND_107") (pintype "power_in"))
      (node (ref "S1") (pin "114") (pinfunction "GND_114") (pintype "power_in"))
      (node (ref "S1") (pin "117") (pinfunction "GND_117") (pintype "power_in"))
      (node (ref "S1") (pin "120") (pinfunction "GND_120") (pintype "power_in"))
      (node (ref "S1") (pin "127") (pinfunction "GND_127") (pintype "power_in"))
      (node (ref "S1") (pin "128") (pinfunction "GND_128") (pintype "power_in"))
      (node (ref "S1") (pin "20") (pinfunction "GND_20") (pintype "power_in"))
      (node (ref "S1") (pin "27") (pinfunction "GND_27") (pintype "power_in"))
      (node (ref "S1") (pin "30") (pinfunction "GND_30") (pintype "power_in"))
      (node (ref "S1") (pin "37") (pinfunction "GND_37") (pintype "power_in"))
      (node (ref "S1") (pin "41") (pinfunction "GND_41") (pintype "power_in"))
      (node (ref "S1") (pin "42") (pinfunction "GND_42") (pintype "power_in"))
      (node (ref "S1") (pin "50") (pinfunction "GND_50") (pintype "power_in"))
      (node (ref "S1") (pin "55") (pinfunction "GND_55") (pintype "power_in"))
      (node (ref "S1") (pin "61") (pinfunction "GND_61") (pintype "power_in"))
      (node (ref "S1") (pin "64") (pinfunction "GND_64") (pintype "power_in"))
      (node (ref "S1") (pin "67") (pinfunction "GND_67") (pintype "power_in"))
      (node (ref "S1") (pin "70") (pinfunction "GND_70") (pintype "power_in"))
      (node (ref "S1") (pin "73") (pinfunction "GND_73") (pintype "power_in"))
      (node (ref "S1") (pin "76") (pinfunction "GND_76") (pintype "power_in"))
      (node (ref "S1") (pin "79") (pinfunction "GND_79") (pintype "power_in"))
      (node (ref "S1") (pin "82") (pinfunction "GND_82") (pintype "power_in"))
      (node (ref "S1") (pin "85") (pinfunction "GND_85") (pintype "power_in"))
      (node (ref "S1") (pin "88") (pinfunction "GND_88") (pintype "power_in"))
      (node (ref "S1") (pin "91") (pinfunction "GND_91") (pintype "power_in"))
      (node (ref "S1") (pin "94") (pinfunction "GND_94") (pintype "power_in"))
      (node (ref "S1") (pin "95") (pinfunction "GND_95") (pintype "power_in"))
      (node (ref "S1") (pin "S1") (pinfunction "GND_S1") (pintype "passive"))
      (node (ref "S1") (pin "S2") (pinfunction "GND_S2") (pintype "power_in"))
      (node (ref "TF1") (pin "10") (pinfunction "GND_10") (pintype "passive"))
      (node (ref "TF1") (pin "6") (pinfunction "VSS_6") (pintype "passive"))
      (node (ref "U1") (pin "7") (pinfunction "GND_7") (pintype "passive"))
      (node (ref "U1") (pin "9") (pinfunction "GND_9") (pintype "passive"))
      (node (ref "U2") (pin "1") (pinfunction "GND3_1") (pintype "power_in"))
      (node (ref "U2") (pin "12") (pinfunction "GND1_12") (pintype "power_in"))
      (node (ref "U2") (pin "13") (pinfunction "GND1_13") (pintype "power_in"))
      (node (ref "U2") (pin "15") (pinfunction "AGND_15") (pintype "power_in"))
      (node (ref "U2") (pin "17") (pinfunction "AGND_17") (pintype "power_in"))
      (node (ref "U2") (pin "21") (pinfunction "GND/ExposedPad_21") (pintype "power_in"))
      (node (ref "U2") (pin "4") (pinfunction "GND2_4") (pintype "power_in"))
      (node (ref "U2") (pin "5") (pinfunction "GND2_5") (pintype "power_in"))
      (node (ref "U3") (pin "1") (pinfunction "GND_1") (pintype "power_in"))
      (node (ref "U4") (pin "7") (pinfunction "GND_7") (pintype "power_in"))
      (node (ref "U5") (pin "4") (pinfunction "VSS_4") (pintype "power_in"))
      (node (ref "VT1") (pin "2") (pinfunction "E_2") (pintype "passive"))
    )
    (net (code "72") (name "LDO9_2V95") (class "Default")
      (node (ref "R13") (pin "2") (pinfunction "2_2") (pintype "passive"))
      (node (ref "S1") (pin "48") (pinfunction "LDO9_2V95/1V8_48") (pintype "output"))
      (node (ref "S1") (pin "52") (pinfunction "VIO_MMC_52") (pintype "input"))
    )
    (net (code "73") (name "LDO16_2V95") (class "Default")
      (node (ref "C23") (pin "1") (pinfunction "1_1") (pintype "passive"))
      (node (ref "C24") (pin "1") (pinfunction "1_1") (pintype "passive"))
      (node (ref "S1") (pin "58") (pinfunction "LDO16_2V95_58") (pintype "output"))
      (node (ref "S1") (pin "60") (pinfunction "LDO16_2V95_60") (pintype "output"))
      (node (ref "TF1") (pin "4") (pinfunction "VDD_4") (pintype "passive"))
    )
    (net (code "74") (name "Net-(C7-Pad2)") (class "Default")
      (node (ref "C7") (pin "2") (pinfunction "2_2") (pintype "passive"))
      (node (ref "R7") (pin "1") (pinfunction "1_1") (pintype "passive"))
    )
    (net (code "75") (name "Net-(D1-C)") (class "Default")
      (node (ref "C1") (pin "1") (pinfunction "1_1") (pintype "passive"))
      (node (ref "D1") (pin "1") (pinfunction "C_1") (pintype "passive"))
      (node (ref "L1") (pin "1") (pinfunction "1_1") (pintype "passive"))
      (node (ref "U1") (pin "8") (pinfunction "SW_8") (pintype "passive"))
    )
    (net (code "76") (name "Net-(D2-A)") (class "Default")
      (node (ref "D2") (pin "1") (pinfunction "A_1") (pintype "passive"))
      (node (ref "R35") (pin "2") (pinfunction "2_2") (pintype "passive"))
    )
    (net (code "77") (name "Net-(D2-K)") (class "Default")
      (node (ref "D2") (pin "2") (pinfunction "K_2") (pintype "passive"))
      (node (ref "VT1") (pin "3") (pinfunction "C_3") (pintype "passive"))
    )
    (net (code "78") (name "Net-(D3-A)") (class "Default")
      (node (ref "D3") (pin "1") (pinfunction "A_1") (pintype "passive"))
      (node (ref "R36") (pin "2") (pinfunction "2_2") (pintype "passive"))
    )
    (net (code "79") (name "Net-(Q1-D)") (class "Default")
      (node (ref "P2") (pin "2") (pinfunction "2_2") (pintype "passive"))
      (node (ref "Q1") (pin "3") (pinfunction "D_3") (pintype "passive"))
    )
    (net (code "80") (name "Net-(Q1-G)") (class "Default")
      (node (ref "Q1") (pin "1") (pinfunction "G_1") (pintype "passive"))
      (node (ref "R38") (pin "2") (pinfunction "2_2") (pintype "passive"))
    )
    (net (code "81") (name "Net-(S1-BOOT_MD0)") (class "Default")
      (node (ref "R11") (pin "1") (pinfunction "1_1") (pintype "passive"))
      (node (ref "S1") (pin "24") (pinfunction "BOOT_MD0_24") (pintype "input"))
    )
    (net (code "82") (name "Net-(S1-BOOT_MD1)") (class "Default")
      (node (ref "R3") (pin "2") (pinfunction "2_2") (pintype "passive"))
      (node (ref "S1") (pin "18") (pinfunction "BOOT_MD1_18") (pintype "input"))
    )
    (net (code "83") (name "Net-(S1-BOOT_MD2)") (class "Default")
      (node (ref "R12") (pin "1") (pinfunction "1_1") (pintype "passive"))
      (node (ref "S1") (pin "22") (pinfunction "BOOT_MD2_22") (pintype "input"))
    )
    (net (code "84") (name "Net-(S1-PCIE_EP_RC_FLAG)") (class "Default")
      (node (ref "R10") (pin "1") (pinfunction "1_1") (pintype "passive"))
      (node (ref "S1") (pin "28") (pinfunction "PCIE_EP_RC_FLAG_28") (pintype "input"))
    )
    (net (code "85") (name "Net-(S1-P_DETECT_IN)") (class "Default")
      (node (ref "R5") (pin "2") (pinfunction "2_2") (pintype "passive"))
      (node (ref "S1") (pin "19") (pinfunction "P_DETECT_IN_19") (pintype "output"))
    )
    (net (code "86") (name "Net-(S1-SLOT_SEL0)") (class "Default")
      (node (ref "R21") (pin "2") (pinfunction "2_2") (pintype "passive"))
      (node (ref "S1") (pin "110") (pinfunction "SLOT_SEL0_110") (pintype "input"))
    )
    (net (code "87") (name "Net-(S1-SLOT_SEL1)") (class "Default")
      (node (ref "R20") (pin "2") (pinfunction "2_2") (pintype "passive"))
      (node (ref "S1") (pin "108") (pinfunction "SLOT_SEL1_108") (pintype "input"))
    )
    (net (code "88") (name "Net-(S1-SPI2_MOSI)") (class "Default")
      (node (ref "R24") (pin "1") (pinfunction "1_1") (pintype "passive"))
      (node (ref "S1") (pin "119") (pinfunction "SPI2_MOSI_119") (pintype "output"))
    )
    (net (code "89") (name "Net-(S1-USB3_RX_N)") (class "Default")
      (node (ref "C14") (pin "1") (pinfunction "1_1") (pintype "passive"))
      (node (ref "S1") (pin "83") (pinfunction "USB3_RX_N_83") (pintype "input"))
    )
    (net (code "90") (name "Net-(S1-USB3_RX_P)") (class "Default")
      (node (ref "C13") (pin "1") (pinfunction "1_1") (pintype "passive"))
      (node (ref "S1") (pin "81") (pinfunction "USB3_RX_P_81") (pintype "input"))
    )
    (net (code "91") (name "Net-(S1-USB_VBUS)") (class "Default")
      (node (ref "R22") (pin "1") (pinfunction "1_1") (pintype "passive"))
      (node (ref "S1") (pin "111") (pinfunction "USB_VBUS_111") (pintype "input"))
    )
    (net (code "92") (name "Net-(TF1-SW)") (class "Default")
      (node (ref "R39") (pin "1") (pinfunction "1_1") (pintype "passive"))
      (node (ref "TF1") (pin "9") (pinfunction "SW_9") (pintype "passive"))
    )
    (net (code "93") (name "Net-(U1-BOOT)") (class "Default")
      (node (ref "C1") (pin "2") (pinfunction "2_2") (pintype "passive"))
      (node (ref "U1") (pin "1") (pinfunction "BOOT_1") (pintype "passive"))
    )
    (net (code "94") (name "Net-(U1-COMP)") (class "Default")
      (node (ref "C6") (pin "2") (pinfunction "2_2") (pintype "passive"))
      (node (ref "R7") (pin "2") (pinfunction "2_2") (pintype "passive"))
      (node (ref "U1") (pin "6") (pinfunction "COMP_6") (pintype "passive"))
    )
    (net (code "95") (name "Net-(U1-EN)") (class "Default")
      (node (ref "R4") (pin "1") (pinfunction "1_1") (pintype "passive"))
      (node (ref "R8") (pin "2") (pinfunction "2_2") (pintype "passive"))
      (node (ref "U1") (pin "3") (pinfunction "EN_3") (pintype "passive"))
    )
    (net (code "96") (name "Net-(U1-RT{slash}CLK)") (class "Default")
      (node (ref "R9") (pin "2") (pinfunction "2_2") (pintype "passive"))
      (node (ref "U1") (pin "4") (pinfunction "RT/CLK_4") (pintype "passive"))
    )
    (net (code "97") (name "Net-(U2A-FB1)") (class "Default")
      (node (ref "R14") (pin "1") (pinfunction "1_1") (pintype "passive"))
      (node (ref "R16") (pin "2") (pinfunction "2_2") (pintype "passive"))
      (node (ref "U2") (pin "14") (pinfunction "FB1_14") (pintype "passive"))
    )
    (net (code "98") (name "Net-(U2A-LX1)") (class "Default")
      (node (ref "L2") (pin "1") (pintype "passive"))
      (node (ref "U2") (pin "11") (pinfunction "LX1_11") (pintype "passive"))
    )
    (net (code "99") (name "Net-(U2B-FB2)") (class "Default")
      (node (ref "R18") (pin "1") (pinfunction "1_1") (pintype "passive"))
      (node (ref "R19") (pin "2") (pinfunction "2_2") (pintype "passive"))
      (node (ref "U2") (pin "3") (pinfunction "FB2_3") (pintype "passive"))
    )
    (net (code "100") (name "Net-(U2B-LX2)") (class "Default")
      (node (ref "L4") (pin "1") (pintype "passive"))
      (node (ref "U2") (pin "6") (pinfunction "LX2_6") (pintype "passive"))
    )
    (net (code "101") (name "Net-(U2C-FB3)") (class "Default")
      (node (ref "R15") (pin "1") (pinfunction "1_1") (pintype "passive"))
      (node (ref "R17") (pin "2") (pinfunction "2_2") (pintype "passive"))
      (node (ref "U2") (pin "2") (pinfunction "FB3_2") (pintype "passive"))
    )
    (net (code "102") (name "Net-(U2C-LX3)") (class "Default")
      (node (ref "L3") (pin "1") (pintype "passive"))
      (node (ref "U2") (pin "20") (pinfunction "LX3_20") (pintype "passive"))
    )
    (net (code "103") (name "Net-(U3-EN)") (class "Default")
      (node (ref "C18") (pin "2") (pinfunction "2_2") (pintype "passive"))
      (node (ref "R25") (pin "2") (pinfunction "2_2") (pintype "passive"))
      (node (ref "U3") (pin "7") (pinfunction "VREF2_7") (pintype "power_in"))
      (node (ref "U3") (pin "8") (pinfunction "EN_8") (pintype "input"))
    )
    (net (code "104") (name "Net-(U4-OE)") (class "Default")
      (node (ref "C21") (pin "2") (pinfunction "2_2") (pintype "passive"))
      (node (ref "R33") (pin "1") (pinfunction "1_1") (pintype "passive"))
      (node (ref "U4") (pin "8") (pinfunction "OE_8") (pintype "input"))
    )
    (net (code "105") (name "Net-(U5-A0)") (class "Default")
      (node (ref "R34") (pin "1") (pinfunction "1_1") (pintype "passive"))
      (node (ref "U5") (pin "1") (pinfunction "A0_1") (pintype "input"))
      (node (ref "U5") (pin "2") (pinfunction "A1_2") (pintype "input"))
      (node (ref "U5") (pin "3") (pinfunction "A2_3") (pintype "input"))
    )
    (net (code "106") (name "Net-(U5-WP)") (class "Default")
      (node (ref "R32") (pin "2") (pinfunction "2_2") (pintype "passive"))
      (node (ref "U5") (pin "7") (pinfunction "WP_7") (pintype "input"))
    )
    (net (code "107") (name "Net-(VT1-B)") (class "Default")
      (node (ref "R37") (pin "2") (pinfunction "2_2") (pintype "passive"))
      (node (ref "VT1") (pin "1") (pinfunction "B_1") (pintype "passive"))
    )
    (net (code "108") (name "VBUCK8_1V8") (class "Default")
      (node (ref "R2") (pin "1") (pinfunction "1_1") (pintype "passive"))
      (node (ref "R23") (pin "2") (pinfunction "2_2") (pintype "passive"))
      (node (ref "R24") (pin "2") (pinfunction "2_2") (pintype "passive"))
      (node (ref "R3") (pin "1") (pinfunction "1_1") (pintype "passive"))
      (node (ref "R40") (pin "1") (pinfunction "1_1") (pintype "passive"))
      (node (ref "R5") (pin "1") (pinfunction "1_1") (pintype "passive"))
      (node (ref "S1") (pin "56") (pinfunction "VBUCK8_1V8_56") (pintype "output"))
    )
    (net (code "109") (name "VBUS") (class "Default")
      (node (ref "J1") (pin "A4") (pinfunction "VBUS1_A4") (pintype "passive"))
      (node (ref "J1") (pin "A9") (pinfunction "VBUS1_A9") (pintype "passive"))
      (node (ref "J1") (pin "B4") (pinfunction "VBUS2_B4") (pintype "passive"))
      (node (ref "J1") (pin "B9") (pinfunction "VBUS2_B9") (pintype "passive"))
      (node (ref "R22") (pin "2") (pinfunction "2_2") (pintype "passive"))
    )
    (net (code "110") (name "VCC_1V05") (class "Default")
      (node (ref "C8") (pin "1") (pinfunction "1_1") (pintype "passive"))
      (node (ref "C9") (pin "1") (pinfunction "1_1") (pintype "passive"))
      (node (ref "L2") (pin "2") (pinfunction "2_2") (pintype "passive"))
      (node (ref "R14") (pin "2") (pinfunction "2_2") (pintype "passive"))
      (node (ref "T3") (pin "0") (pinfunction "0_0") (pintype "passive"))
    )
    (net (code "111") (name "VCC_1V8") (class "Default")
      (node (ref "C10") (pin "1") (pinfunction "1_1") (pintype "passive"))
      (node (ref "C11") (pin "1") (pinfunction "1_1") (pintype "passive"))
      (node (ref "C17") (pin "2") (pinfunction "2_2") (pintype "passive"))
      (node (ref "C19") (pin "2") (pinfunction "2_2") (pintype "passive"))
      (node (ref "L3") (pin "2") (pinfunction "2_2") (pintype "passive"))
      (node (ref "R15") (pin "2") (pinfunction "2_2") (pintype "passive"))
      (node (ref "R33") (pin "2") (pinfunction "2_2") (pintype "passive"))
      (node (ref "T1") (pin "0") (pinfunction "0_0") (pintype "passive"))
      (node (ref "U3") (pin "2") (pinfunction "VREF1_2") (pintype "power_in"))
      (node (ref "U4") (pin "1") (pinfunction "VCCA_1") (pintype "power_in"))
    )
    (net (code "112") (name "VCC_3V3") (class "Default")
      (node (ref "C15") (pin "1") (pinfunction "1_1") (pintype "passive"))
      (node (ref "C16") (pin "1") (pinfunction "1_1") (pintype "passive"))
      (node (ref "C20") (pin "2") (pinfunction "2_2") (pintype "passive"))
      (node (ref "C22") (pin "2") (pinfunction "2_2") (pintype "passive"))
      (node (ref "L4") (pin "2") (pinfunction "2_2") (pintype "passive"))
      (node (ref "P1") (pin "28") (pinfunction "28_28") (pintype "passive"))
      (node (ref "R18") (pin "2") (pinfunction "2_2") (pintype "passive"))
      (node (ref "R25") (pin "1") (pinfunction "1_1") (pintype "passive"))
      (node (ref "R26") (pin "1") (pinfunction "1_1") (pintype "passive"))
      (node (ref "R27") (pin "1") (pinfunction "1_1") (pintype "passive"))
      (node (ref "R28") (pin "1") (pinfunction "1_1") (pintype "passive"))
      (node (ref "R29") (pin "1") (pinfunction "1_1") (pintype "passive"))
      (node (ref "R30") (pin "1") (pinfunction "1_1") (pintype "passive"))
      (node (ref "R31") (pin "1") (pinfunction "1_1") (pintype "passive"))
      (node (ref "R34") (pin "2") (pinfunction "2_2") (pintype "passive"))
      (node (ref "R35") (pin "1") (pinfunction "1_1") (pintype "passive"))
      (node (ref "R36") (pin "1") (pinfunction "1_1") (pintype "passive"))
      (node (ref "T2") (pin "0") (pinfunction "0_0") (pintype "passive"))
      (node (ref "U4") (pin "14") (pinfunction "VCCB_14") (pintype "power_in"))
      (node (ref "U5") (pin "8") (pinfunction "VCC_8") (pintype "power_in"))
    )
    (net (code "113") (name "VCC_USB_5V_2") (class "Default")
      (node (ref "P1") (pin "27") (pinfunction "27_27") (pintype "passive"))
      (node (ref "P2") (pin "3") (pinfunction "3_3") (pintype "passive"))
      (node (ref "Q1") (pin "2") (pinfunction "S_2") (pintype "passive"))
    )
    (net (code "114") (name "VIN") (class "Default")
      (node (ref "C5") (pin "2") (pinfunction "2_2") (pintype "passive"))
      (node (ref "CON1") (pin "1") (pinfunction "1_1") (pintype "power_in"))
      (node (ref "R4") (pin "2") (pinfunction "2_2") (pintype "passive"))
      (node (ref "U1") (pin "2") (pinfunction "VIN_2") (pintype "passive"))
    )
    (net (code "115") (name "VSYS_3V8") (class "Default")
      (node (ref "C12") (pin "2") (pinfunction "2_2") (pintype "passive"))
      (node (ref "C2") (pin "2") (pinfunction "2_2") (pintype "passive"))
      (node (ref "C3") (pin "1") (pinfunction "1_1") (pintype "passive"))
      (node (ref "C4") (pin "1") (pinfunction "1_1") (pintype "passive"))
      (node (ref "L1") (pin "2") (pinfunction "2_2") (pintype "passive"))
      (node (ref "P1") (pin "23") (pinfunction "23_23") (pintype "passive"))
      (node (ref "P1") (pin "24") (pinfunction "24_24") (pintype "passive"))
      (node (ref "P1") (pin "25") (pinfunction "25_25") (pintype "passive"))
      (node (ref "P1") (pin "26") (pinfunction "26_26") (pintype "passive"))
      (node (ref "R1") (pin "2") (pinfunction "2_2") (pintype "passive"))
      (node (ref "S1") (pin "1") (pinfunction "VSYS_3V8_1") (pintype "input"))
      (node (ref "S1") (pin "10") (pinfunction "VSYS_3V8_10") (pintype "input"))
      (node (ref "S1") (pin "11") (pinfunction "VSYS_3V8_11") (pintype "input"))
      (node (ref "S1") (pin "12") (pinfunction "VSYS_3V8_12") (pintype "input"))
      (node (ref "S1") (pin "13") (pinfunction "VSYS_3V8_13") (pintype "input"))
      (node (ref "S1") (pin "14") (pinfunction "VSYS_3V8_14") (pintype "input"))
      (node (ref "S1") (pin "15") (pinfunction "VSYS_3V8_15") (pintype "input"))
      (node (ref "S1") (pin "16") (pinfunction "VSYS_3V8_16") (pintype "input"))
      (node (ref "S1") (pin "2") (pinfunction "VSYS_3V8_2") (pintype "input"))
      (node (ref "S1") (pin "3") (pinfunction "VSYS_3V8_3") (pintype "input"))
      (node (ref "S1") (pin "4") (pinfunction "VSYS_3V8_4") (pintype "input"))
      (node (ref "S1") (pin "5") (pinfunction "VSYS_3V8_5") (pintype "input"))
      (node (ref "S1") (pin "6") (pinfunction "VSYS_3V8_6") (pintype "input"))
      (node (ref "S1") (pin "7") (pinfunction "VSYS_3V8_7") (pintype "input"))
      (node (ref "S1") (pin "8") (pinfunction "VSYS_3V8_8") (pintype "input"))
      (node (ref "S1") (pin "9") (pinfunction "VSYS_3V8_9") (pintype "input"))
      (node (ref "U2") (pin "10") (pinfunction "VIN1_10") (pintype "power_in"))
      (node (ref "U2") (pin "16") (pinfunction "VCC_16") (pintype "power_in"))
      (node (ref "U2") (pin "18") (pinfunction "EN3_18") (pintype "passive"))
      (node (ref "U2") (pin "19") (pinfunction "VIN3_19") (pintype "power_in"))
      (node (ref "U2") (pin "7") (pinfunction "VIN2_7") (pintype "power_in"))
      (node (ref "U2") (pin "8") (pinfunction "EN2_8") (pintype "passive"))
      (node (ref "U2") (pin "9") (pinfunction "EN1_9") (pintype "passive"))
    )
    (net (code "116") (name "unconnected-(J1-CC1-PadA5)") (class "Default")
      (node (ref "J1") (pin "A5") (pinfunction "CC1_A5") (pintype "passive"))
    )
    (net (code "117") (name "unconnected-(J1-CC2-PadB5)") (class "Default")
      (node (ref "J1") (pin "B5") (pinfunction "CC2_B5") (pintype "passive"))
    )
    (net (code "118") (name "unconnected-(J1-SBU1-PadA8)") (class "Default")
      (node (ref "J1") (pin "A8") (pinfunction "SBU1_A8") (pintype "passive"))
    )
    (net (code "119") (name "unconnected-(J1-SBU2-PadB8)") (class "Default")
      (node (ref "J1") (pin "B8") (pinfunction "SBU2_B8") (pintype "passive"))
    )
    (net (code "120") (name "unconnected-(S1-ADD_SEL-Pad104)") (class "Default")
      (node (ref "S1") (pin "104") (pinfunction "ADD_SEL_104") (pintype "bidirectional"))
    )
    (net (code "121") (name "unconnected-(S1-EMMC_DATA4-Pad35)") (class "Default")
      (node (ref "S1") (pin "35") (pinfunction "EMMC_DATA4_35") (pintype "bidirectional"))
    )
    (net (code "122") (name "unconnected-(S1-EMMC_DATA5-Pad31)") (class "Default")
      (node (ref "S1") (pin "31") (pinfunction "EMMC_DATA5_31") (pintype "bidirectional"))
    )
    (net (code "123") (name "unconnected-(S1-EMMC_DATA6-Pad33)") (class "Default")
      (node (ref "S1") (pin "33") (pinfunction "EMMC_DATA6_33") (pintype "bidirectional"))
    )
    (net (code "124") (name "unconnected-(S1-EMMC_DATA7-Pad29)") (class "Default")
      (node (ref "S1") (pin "29") (pinfunction "EMMC_DATA7_29") (pintype "bidirectional"))
    )
    (net (code "125") (name "unconnected-(S1-LDO15_2V95-Pad54)") (class "Default")
      (node (ref "S1") (pin "54") (pinfunction "LDO15_2V95_54") (pintype "output"))
    )
    (net (code "126") (name "unconnected-(S1-NC-Pad143)") (class "Default")
      (node (ref "S1") (pin "143") (pinfunction "NC_143") (pintype "passive"))
    )
    (net (code "127") (name "unconnected-(S1-NC-Pad144)") (class "Default")
      (node (ref "S1") (pin "144") (pinfunction "NC_144") (pintype "passive"))
    )
    (net (code "128") (name "unconnected-(S1-PCIE_RX1_N-Pad65)") (class "Default")
      (node (ref "S1") (pin "65") (pinfunction "PCIE_RX1_N_65") (pintype "input"))
    )
    (net (code "129") (name "unconnected-(S1-PCIE_RX1_P-Pad63)") (class "Default")
      (node (ref "S1") (pin "63") (pinfunction "PCIE_RX1_P_63") (pintype "input"))
    )
    (net (code "130") (name "unconnected-(S1-PCIE_RX2_N-Pad71)") (class "Default")
      (node (ref "S1") (pin "71") (pinfunction "PCIE_RX2_N_71") (pintype "input"))
    )
    (net (code "131") (name "unconnected-(S1-PCIE_RX2_P-Pad69)") (class "Default")
      (node (ref "S1") (pin "69") (pinfunction "PCIE_RX2_P_69") (pintype "input"))
    )
    (net (code "132") (name "unconnected-(S1-PCIE_RX3_N-Pad77)") (class "Default")
      (node (ref "S1") (pin "77") (pinfunction "PCIE_RX3_N_77") (pintype "input"))
    )
    (net (code "133") (name "unconnected-(S1-PCIE_RX3_P-Pad75)") (class "Default")
      (node (ref "S1") (pin "75") (pinfunction "PCIE_RX3_P_75") (pintype "input"))
    )
    (net (code "134") (name "unconnected-(S1-PCIE_TX1_N-Pad74)") (class "Default")
      (node (ref "S1") (pin "74") (pinfunction "PCIE_TX1_N_74") (pintype "output"))
    )
    (net (code "135") (name "unconnected-(S1-PCIE_TX1_P-Pad72)") (class "Default")
      (node (ref "S1") (pin "72") (pinfunction "PCIE_TX1_P_72") (pintype "output"))
    )
    (net (code "136") (name "unconnected-(S1-PCIE_TX2_N-Pad80)") (class "Default")
      (node (ref "S1") (pin "80") (pinfunction "PCIE_TX2_N_80") (pintype "output"))
    )
    (net (code "137") (name "unconnected-(S1-PCIE_TX2_P-Pad78)") (class "Default")
      (node (ref "S1") (pin "78") (pinfunction "PCIE_TX2_P_78") (pintype "output"))
    )
    (net (code "138") (name "unconnected-(S1-PCIE_TX3_N-Pad86)") (class "Default")
      (node (ref "S1") (pin "86") (pinfunction "PCIE_TX3_N_86") (pintype "output"))
    )
    (net (code "139") (name "unconnected-(S1-PCIE_TX3_P-Pad84)") (class "Default")
      (node (ref "S1") (pin "84") (pinfunction "PCIE_TX3_P_84") (pintype "output"))
    )
    (net (code "140") (name "unconnected-(S1-SPI2_CLK-Pad121)") (class "Default")
      (node (ref "S1") (pin "121") (pinfunction "SPI2_CLK_121") (pintype "output"))
    )
    (net (code "141") (name "unconnected-(S1-SPI2_CS_N-Pad125)") (class "Default")
      (node (ref "S1") (pin "125") (pinfunction "SPI2_CS_N_125") (pintype "output"))
    )
    (net (code "142") (name "unconnected-(S1-SPI2_MISO-Pad123)") (class "Default")
      (node (ref "S1") (pin "123") (pinfunction "SPI2_MISO_123") (pintype "input"))
    )
    (net (code "143") (name "unconnected-(U4-NC-Pad6)") (class "Default")
      (node (ref "U4") (pin "6") (pinfunction "NC_6") (pintype "passive"))
    )
    (net (code "144") (name "unconnected-(U4-NC-Pad9)") (class "Default")
      (node (ref "U4") (pin "9") (pinfunction "NC_9") (pintype "passive"))
    )
  )
)
